# controller.net
KiCad netlist of a schematic drawn in EAGLE
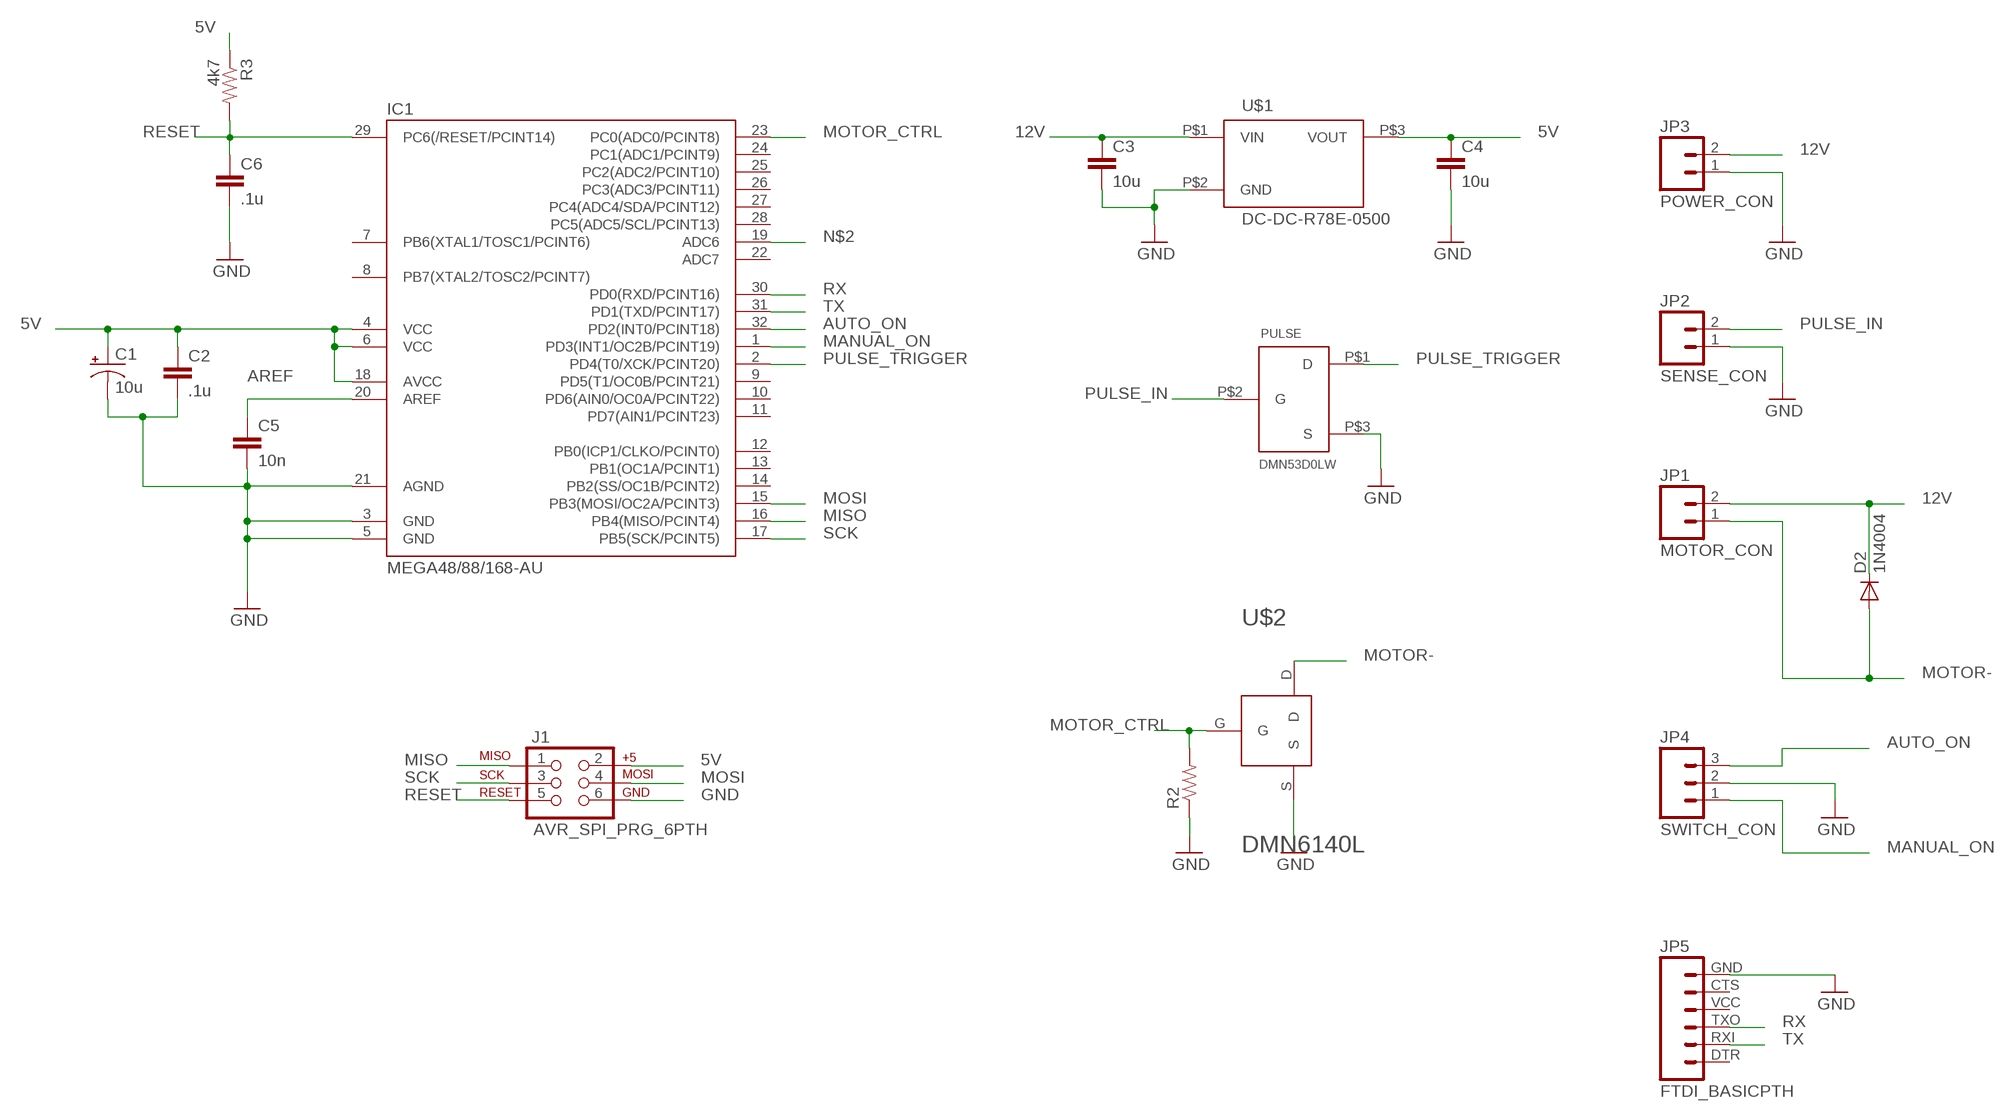
[diagram p0: schematic, sheet 1]

(export (version "E")
  (design (tool "Eeschema 10.0.6"))
  (components
    (comp (ref "C1")
      (value "10u")
      (footprint "eagle-import:EIA3216")
      (libsource (lib "eagle-import") (part "CAP_POL1206"))
    )
    (comp (ref "C2")
      (value ".1u")
      (footprint "eagle-import:0805")
      (libsource (lib "eagle-import") (part "CAP0805"))
    )
    (comp (ref "C3")
      (value "10u")
      (footprint "eagle-import:0805")
      (libsource (lib "eagle-import") (part "CAP0805"))
    )
    (comp (ref "C4")
      (value "10u")
      (footprint "eagle-import:0805")
      (libsource (lib "eagle-import") (part "CAP0805"))
    )
    (comp (ref "C5")
      (value "10n")
      (footprint "eagle-import:0805")
      (libsource (lib "eagle-import") (part "CAP0805"))
    )
    (comp (ref "C6")
      (value ".1u")
      (footprint "eagle-import:0805")
      (libsource (lib "eagle-import") (part "CAP0805"))
    )
    (comp (ref "D2")
      (value "1N4004")
      (footprint "eagle-import:DO41-10")
      (libsource (lib "eagle-import") (part "1N4004"))
    )
    (comp (ref "IC1")
      (value "MEGA48/88/168-AU")
      (footprint "eagle-import:TQFP32-08")
      (libsource (lib "eagle-import") (part "MEGA48/88/168-AU"))
    )
    (comp (ref "J1")
      (value "AVR_SPI_PRG_6PTH")
      (footprint "eagle-import:2X3")
      (libsource (lib "eagle-import") (part "AVR_SPI_PRG_6PTH"))
    )
    (comp (ref "JP1")
      (value "MOTOR_CON")
      (footprint "eagle-import:1X02_LONGPADS")
      (libsource (lib "eagle-import") (part "M02"))
    )
    (comp (ref "JP2")
      (value "SENSE_CON")
      (footprint "eagle-import:1X02_LONGPADS")
      (libsource (lib "eagle-import") (part "M02"))
    )
    (comp (ref "JP3")
      (value "POWER_CON")
      (footprint "eagle-import:1X02_LONGPADS")
      (libsource (lib "eagle-import") (part "M02"))
    )
    (comp (ref "JP4")
      (value "SWITCH_CON")
      (footprint "eagle-import:1X03_NO_SILK")
      (libsource (lib "eagle-import") (part "M031X03_NO_SILK"))
    )
    (comp (ref "JP5")
      (value "FTDI_BASICPTH")
      (footprint "eagle-import:FTDI_BASIC")
      (libsource (lib "eagle-import") (part "FTDI_BASICPTH"))
    )
    (comp (ref "PULSE")
      (value "DMN53D0LW")
      (footprint "eagle-import:SOT-323")
      (libsource (lib "eagle-import") (part "DMN53D0LW"))
    )
    (comp (ref "R2")
      (value "RESISTOR1206")
      (footprint "eagle-import:1206")
      (libsource (lib "eagle-import") (part "RESISTOR1206"))
    )
    (comp (ref "R3")
      (value "4k7")
      (footprint "eagle-import:1206")
      (libsource (lib "eagle-import") (part "RESISTOR1206"))
    )
    (comp (ref "U$1")
      (value "DC-DC-R78E-0500")
      (footprint "eagle-import:DC-DC-R78E-0500")
      (libsource (lib "eagle-import") (part "DC-DC-R78E-0500"))
    )
    (comp (ref "U$2")
      (value "DMN6140L")
      (footprint "eagle-import:SOT-32-DIODES")
      (libsource (lib "eagle-import") (part "DMN6140L"))
    )
  )
  (nets
    (net (code "1") (name "/5V") (class "Default")
      (node (ref "C1") (pin "A") (pinfunction "+_A") (pintype "passive"))
      (node (ref "C2") (pin "1") (pinfunction "1_1") (pintype "passive"))
      (node (ref "C4") (pin "1") (pinfunction "1_1") (pintype "passive"))
      (node (ref "IC1") (pin "18") (pinfunction "AVCC_18") (pintype "passive"))
      (node (ref "IC1") (pin "4") (pinfunction "VCC_4") (pintype "power_in"))
      (node (ref "IC1") (pin "6") (pinfunction "VCC_6") (pintype "power_in"))
      (node (ref "J1") (pin "2") (pinfunction "2_2") (pintype "passive"))
      (node (ref "R3") (pin "1") (pinfunction "1_1") (pintype "passive"))
      (node (ref "U$1") (pin "P$3") (pinfunction "VOUT_P$3") (pintype "bidirectional"))
    )
    (net (code "2") (name "/12V") (class "Default")
      (node (ref "C3") (pin "1") (pinfunction "1_1") (pintype "passive"))
      (node (ref "D2") (pin "C") (pinfunction "C_C") (pintype "passive"))
      (node (ref "JP1") (pin "2") (pinfunction "2_2") (pintype "passive"))
      (node (ref "JP3") (pin "2") (pinfunction "2_2") (pintype "passive"))
      (node (ref "U$1") (pin "P$1") (pinfunction "VIN_P$1") (pintype "bidirectional"))
    )
    (net (code "3") (name "/AREF") (class "Default")
      (node (ref "C5") (pin "1") (pinfunction "1_1") (pintype "passive"))
      (node (ref "IC1") (pin "20") (pinfunction "AREF_20") (pintype "passive"))
    )
    (net (code "4") (name "/AUTO_ON") (class "Default")
      (node (ref "IC1") (pin "32") (pinfunction "PD2(INT0/PCINT18)_32") (pintype "bidirectional"))
      (node (ref "JP4") (pin "3") (pinfunction "3_3") (pintype "passive"))
    )
    (net (code "5") (name "/MANUAL_ON") (class "Default")
      (node (ref "IC1") (pin "1") (pinfunction "PD3(INT1/OC2B/PCINT19)_1") (pintype "bidirectional"))
      (node (ref "JP4") (pin "1") (pinfunction "1_1") (pintype "passive"))
    )
    (net (code "6") (name "/MISO") (class "Default")
      (node (ref "IC1") (pin "16") (pinfunction "PB4(MISO/PCINT4)_16") (pintype "bidirectional"))
      (node (ref "J1") (pin "1") (pinfunction "1_1") (pintype "passive"))
    )
    (net (code "7") (name "/MOSI") (class "Default")
      (node (ref "IC1") (pin "15") (pinfunction "PB3(MOSI/OC2A/PCINT3)_15") (pintype "bidirectional"))
      (node (ref "J1") (pin "4") (pinfunction "4_4") (pintype "passive"))
    )
    (net (code "8") (name "/MOTOR-") (class "Default")
      (node (ref "D2") (pin "A") (pinfunction "A_A") (pintype "passive"))
      (node (ref "JP1") (pin "1") (pinfunction "1_1") (pintype "passive"))
      (node (ref "U$2") (pin "D") (pinfunction "D_D") (pintype "bidirectional"))
    )
    (net (code "9") (name "/MOTOR_CTRL") (class "Default")
      (node (ref "IC1") (pin "23") (pinfunction "PC0(ADC0/PCINT8)_23") (pintype "bidirectional"))
      (node (ref "R2") (pin "2") (pinfunction "2_2") (pintype "passive"))
      (node (ref "U$2") (pin "G") (pinfunction "G_G") (pintype "bidirectional"))
    )
    (net (code "10") (name "/N$2") (class "Default")
      (node (ref "IC1") (pin "19") (pinfunction "ADC6_19") (pintype "passive"))
    )
    (net (code "11") (name "/PULSE_IN") (class "Default")
      (node (ref "JP2") (pin "2") (pinfunction "2_2") (pintype "passive"))
      (node (ref "PULSE") (pin "P$2") (pinfunction "G_P$2") (pintype "bidirectional"))
    )
    (net (code "12") (name "/PULSE_TRIGGER") (class "Default")
      (node (ref "IC1") (pin "2") (pinfunction "PD4(T0/XCK/PCINT20)_2") (pintype "bidirectional"))
      (node (ref "PULSE") (pin "P$1") (pinfunction "D_P$1") (pintype "bidirectional"))
    )
    (net (code "13") (name "/RESET") (class "Default")
      (node (ref "C6") (pin "1") (pinfunction "1_1") (pintype "passive"))
      (node (ref "IC1") (pin "29") (pinfunction "PC6(/RESET/PCINT14)_29") (pintype "bidirectional"))
      (node (ref "J1") (pin "5") (pinfunction "5_5") (pintype "passive"))
      (node (ref "R3") (pin "2") (pinfunction "2_2") (pintype "passive"))
    )
    (net (code "14") (name "/RX") (class "Default")
      (node (ref "IC1") (pin "30") (pinfunction "PD0(RXD/PCINT16)_30") (pintype "bidirectional"))
      (node (ref "JP5") (pin "TXO") (pinfunction "3_TXO") (pintype "passive"))
    )
    (net (code "15") (name "/SCK") (class "Default")
      (node (ref "IC1") (pin "17") (pinfunction "PB5(SCK/PCINT5)_17") (pintype "bidirectional"))
      (node (ref "J1") (pin "3") (pinfunction "3_3") (pintype "passive"))
    )
    (net (code "16") (name "/TX") (class "Default")
      (node (ref "IC1") (pin "31") (pinfunction "PD1(TXD/PCINT17)_31") (pintype "bidirectional"))
      (node (ref "JP5") (pin "RXI") (pinfunction "2_RXI") (pintype "passive"))
    )
    (net (code "17") (name "GND") (class "Default")
      (node (ref "C1") (pin "C") (pinfunction "-_C") (pintype "passive"))
      (node (ref "C2") (pin "2") (pinfunction "2_2") (pintype "passive"))
      (node (ref "C3") (pin "2") (pinfunction "2_2") (pintype "passive"))
      (node (ref "C4") (pin "2") (pinfunction "2_2") (pintype "passive"))
      (node (ref "C5") (pin "2") (pinfunction "2_2") (pintype "passive"))
      (node (ref "C6") (pin "2") (pinfunction "2_2") (pintype "passive"))
      (node (ref "IC1") (pin "21") (pinfunction "AGND_21") (pintype "power_in"))
      (node (ref "IC1") (pin "3") (pinfunction "GND_3") (pintype "power_in"))
      (node (ref "IC1") (pin "5") (pinfunction "GND_5") (pintype "power_in"))
      (node (ref "J1") (pin "6") (pinfunction "6_6") (pintype "passive"))
      (node (ref "JP2") (pin "1") (pinfunction "1_1") (pintype "passive"))
      (node (ref "JP3") (pin "1") (pinfunction "1_1") (pintype "passive"))
      (node (ref "JP4") (pin "2") (pinfunction "2_2") (pintype "passive"))
      (node (ref "JP5") (pin "GND") (pinfunction "6_GND") (pintype "passive"))
      (node (ref "PULSE") (pin "P$3") (pinfunction "S_P$3") (pintype "bidirectional"))
      (node (ref "R2") (pin "1") (pinfunction "1_1") (pintype "passive"))
      (node (ref "U$1") (pin "P$2") (pinfunction "GND_P$2") (pintype "bidirectional"))
      (node (ref "U$2") (pin "S") (pinfunction "S_S") (pintype "bidirectional"))
    )
    (net (code "18") (name "unconnected-(IC1-ADC7-Pad22)") (class "Default")
      (node (ref "IC1") (pin "22") (pinfunction "ADC7_22") (pintype "passive"))
    )
    (net (code "19") (name "unconnected-(IC1-PB0(ICP1{slash}CLKO{slash}PCINT0)-Pad12)") (class "Default")
      (node (ref "IC1") (pin "12") (pinfunction "PB0(ICP1/CLKO/PCINT0)_12") (pintype "bidirectional"))
    )
    (net (code "20") (name "unconnected-(IC1-PB1(OC1A{slash}PCINT1)-Pad13)") (class "Default")
      (node (ref "IC1") (pin "13") (pinfunction "PB1(OC1A/PCINT1)_13") (pintype "bidirectional"))
    )
    (net (code "21") (name "unconnected-(IC1-PB2(SS{slash}OC1B{slash}PCINT2)-Pad14)") (class "Default")
      (node (ref "IC1") (pin "14") (pinfunction "PB2(SS/OC1B/PCINT2)_14") (pintype "bidirectional"))
    )
    (net (code "22") (name "unconnected-(IC1-PB6(XTAL1{slash}TOSC1{slash}PCINT6)-Pad7)") (class "Default")
      (node (ref "IC1") (pin "7") (pinfunction "PB6(XTAL1/TOSC1/PCINT6)_7") (pintype "bidirectional"))
    )
    (net (code "23") (name "unconnected-(IC1-PB7(XTAL2{slash}TOSC2{slash}PCINT7)-Pad8)") (class "Default")
      (node (ref "IC1") (pin "8") (pinfunction "PB7(XTAL2/TOSC2/PCINT7)_8") (pintype "bidirectional"))
    )
    (net (code "24") (name "unconnected-(IC1-PC1(ADC1{slash}PCINT9)-Pad24)") (class "Default")
      (node (ref "IC1") (pin "24") (pinfunction "PC1(ADC1/PCINT9)_24") (pintype "bidirectional"))
    )
    (net (code "25") (name "unconnected-(IC1-PC2(ADC2{slash}PCINT10)-Pad25)") (class "Default")
      (node (ref "IC1") (pin "25") (pinfunction "PC2(ADC2/PCINT10)_25") (pintype "bidirectional"))
    )
    (net (code "26") (name "unconnected-(IC1-PC3(ADC3{slash}PCINT11)-Pad26)") (class "Default")
      (node (ref "IC1") (pin "26") (pinfunction "PC3(ADC3/PCINT11)_26") (pintype "bidirectional"))
    )
    (net (code "27") (name "unconnected-(IC1-PC4(ADC4{slash}SDA{slash}PCINT12)-Pad27)") (class "Default")
      (node (ref "IC1") (pin "27") (pinfunction "PC4(ADC4/SDA/PCINT12)_27") (pintype "bidirectional"))
    )
    (net (code "28") (name "unconnected-(IC1-PC5(ADC5{slash}SCL{slash}PCINT13)-Pad28)") (class "Default")
      (node (ref "IC1") (pin "28") (pinfunction "PC5(ADC5/SCL/PCINT13)_28") (pintype "bidirectional"))
    )
    (net (code "29") (name "unconnected-(IC1-PD5(T1{slash}OC0B{slash}PCINT21)-Pad9)") (class "Default")
      (node (ref "IC1") (pin "9") (pinfunction "PD5(T1/OC0B/PCINT21)_9") (pintype "bidirectional"))
    )
    (net (code "30") (name "unconnected-(IC1-PD6(AIN0{slash}OC0A{slash}PCINT22)-Pad10)") (class "Default")
      (node (ref "IC1") (pin "10") (pinfunction "PD6(AIN0/OC0A/PCINT22)_10") (pintype "bidirectional"))
    )
    (net (code "31") (name "unconnected-(IC1-PD7(AIN1{slash}PCINT23)-Pad11)") (class "Default")
      (node (ref "IC1") (pin "11") (pinfunction "PD7(AIN1/PCINT23)_11") (pintype "bidirectional"))
    )
    (net (code "32") (name "unconnected-(JP5-1-PadDTR)") (class "Default")
      (node (ref "JP5") (pin "DTR") (pinfunction "1_DTR") (pintype "passive"))
    )
    (net (code "33") (name "unconnected-(JP5-4-PadVCC)") (class "Default")
      (node (ref "JP5") (pin "VCC") (pinfunction "4_VCC") (pintype "passive"))
    )
    (net (code "34") (name "unconnected-(JP5-5-PadCTS)") (class "Default")
      (node (ref "JP5") (pin "CTS") (pinfunction "5_CTS") (pintype "passive"))
    )
  )
)
